# 01_Power.net
KiCad netlist of a schematic drawn in Altium Designer
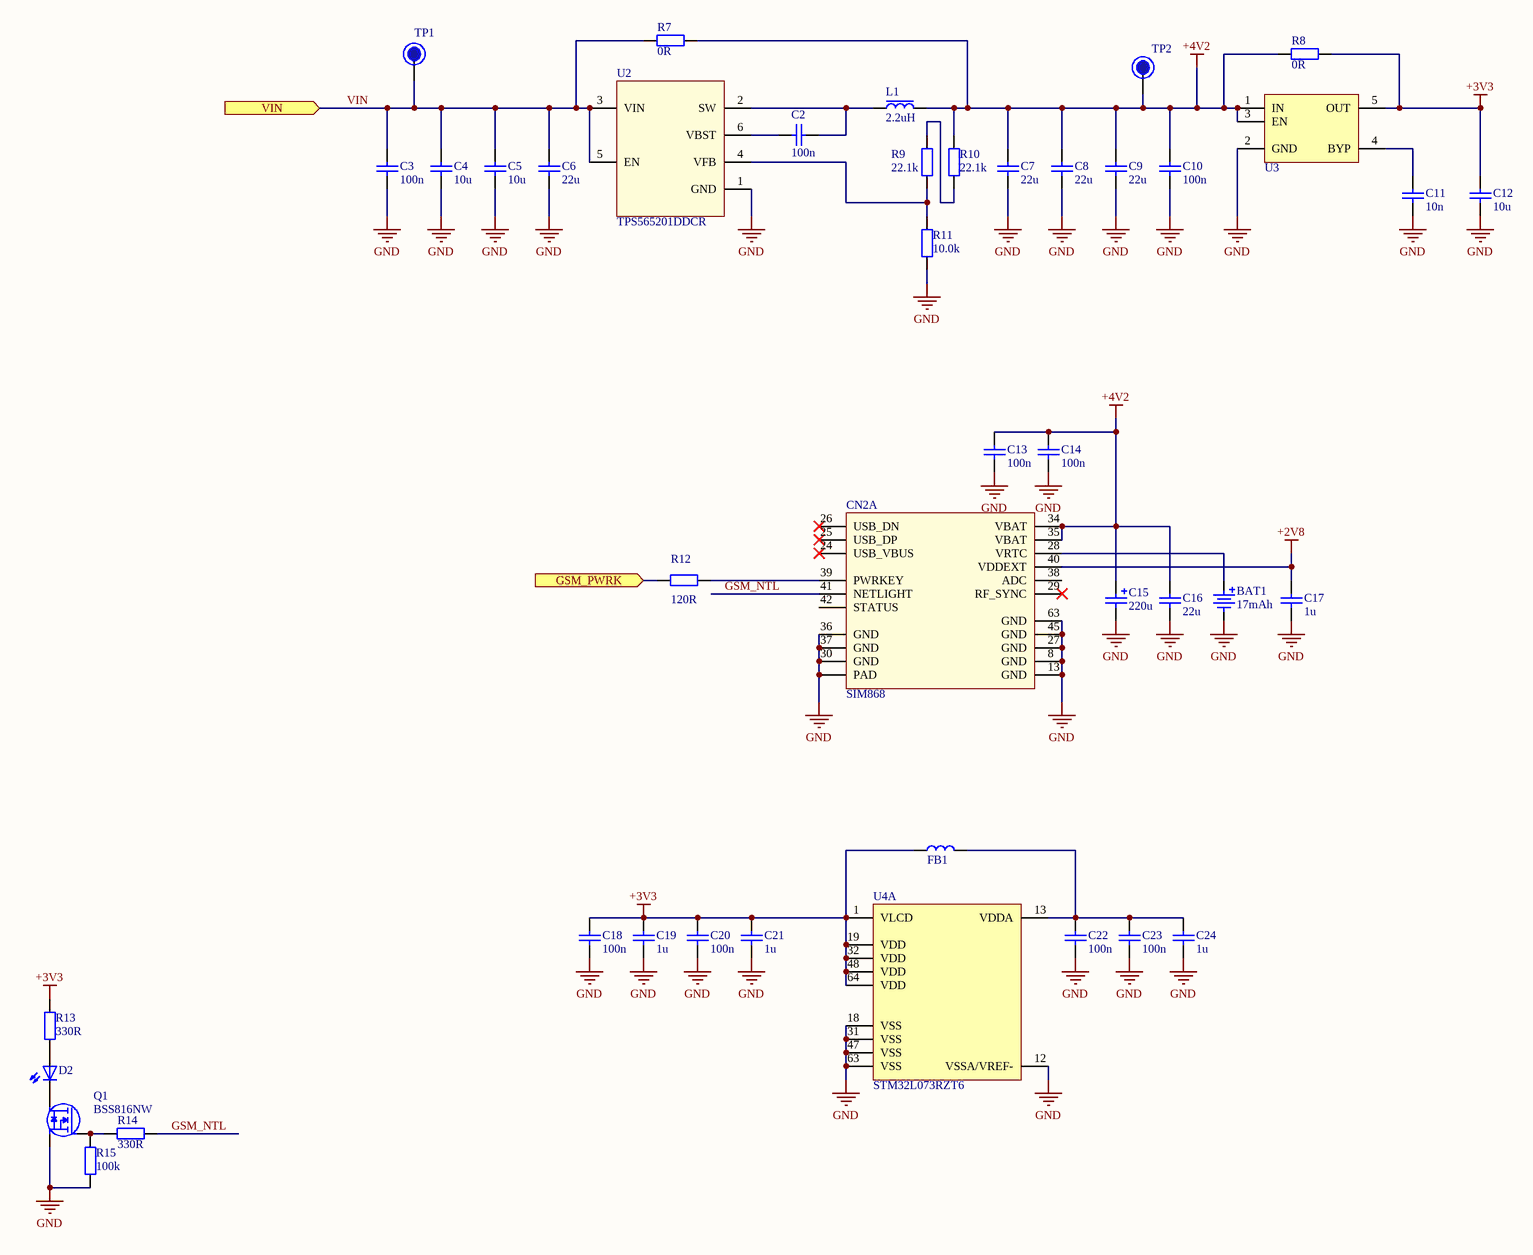
[diagram p0: 01_Power.SchDoc]

(export (version "E")
  (design (tool "Eeschema 10.0.6"))
  (components
    (comp (ref "BAT1")
      (value "17mAh")
      (footprint "ML1220")
      (description "BATT LITH 3V 17MAH COIN 12.5MM")
      (fields (field (name "MANUFACTURER") "CHINA") (field (name "MANUFACTURER PART NUMBER") "ML1220"))
      (libsource (lib "alfasat_lib") (part "ML1220"))
    )
    (comp (ref "C2")
      (value "100n")
      (footprint "C0603_IPC_MD")
      (description "CAP CER 0.1UF 16V X7R 0603")
      (fields
        (field (name "MANUFACTURER") "Samsung Electro-Mechanics")
        (field (name "MANUFACTURER PART NUMBER") "CL10B104KO8NNNC")
      )
      (libsource (lib "alfasat_parts_lib") (part "CL10B104KO8NNNC"))
    )
    (comp (ref "C3")
      (value "100n")
      (footprint "C0603_IPC_MD")
      (description "CAP CER 0.1UF 16V X7R 0603")
      (fields
        (field (name "MANUFACTURER") "Samsung Electro-Mechanics")
        (field (name "MANUFACTURER PART NUMBER") "CL10B104KO8NNNC")
      )
      (libsource (lib "alfasat_parts_lib") (part "CL10B104KO8NNNC"))
    )
    (comp (ref "C4")
      (value "10u")
      (footprint "C0805_IPC_MD")
      (description "CAP CER 10UF 16V X7R 0805")
      (fields
        (field (name "MANUFACTURER") "Samsung Electro-Mechanics")
        (field (name "MANUFACTURER PART NUMBER") "CL21B106KOQNNNG")
      )
      (libsource (lib "alfasat_parts_lib") (part "CL21B106KOQNNNG"))
    )
    (comp (ref "C5")
      (value "10u")
      (footprint "C0805_IPC_MD")
      (description "CAP CER 10UF 16V X7R 0805")
      (fields
        (field (name "MANUFACTURER") "Samsung Electro-Mechanics")
        (field (name "MANUFACTURER PART NUMBER") "CL21B106KOQNNNG")
      )
      (libsource (lib "alfasat_parts_lib") (part "CL21B106KOQNNNG"))
    )
    (comp (ref "C6")
      (value "22u")
      (footprint "C0805_IPC_MD")
      (description "CAP CER 22UF 16V X5R 0805")
      (fields
        (field (name "MANUFACTURER") "Samsung Electro-Mechanics")
        (field (name "MANUFACTURER PART NUMBER") "CL21A226MOCLRNC")
      )
      (libsource (lib "alfasat_parts_lib") (part "CL21A226MOCLRNC"))
    )
    (comp (ref "C7")
      (value "22u")
      (footprint "C0805_IPC_MD")
      (description "CAP CER 22UF 16V X5R 0805")
      (fields
        (field (name "MANUFACTURER") "Samsung Electro-Mechanics")
        (field (name "MANUFACTURER PART NUMBER") "CL21A226MOCLRNC")
      )
      (libsource (lib "alfasat_parts_lib") (part "CL21A226MOCLRNC"))
    )
    (comp (ref "C8")
      (value "22u")
      (footprint "C0805_IPC_MD")
      (description "CAP CER 22UF 16V X5R 0805")
      (fields
        (field (name "MANUFACTURER") "Samsung Electro-Mechanics")
        (field (name "MANUFACTURER PART NUMBER") "CL21A226MOCLRNC")
      )
      (libsource (lib "alfasat_parts_lib") (part "CL21A226MOCLRNC"))
    )
    (comp (ref "C9")
      (value "22u")
      (footprint "C0805_IPC_MD")
      (description "CAP CER 22UF 16V X5R 0805")
      (fields
        (field (name "MANUFACTURER") "Samsung Electro-Mechanics")
        (field (name "MANUFACTURER PART NUMBER") "CL21A226MOCLRNC")
      )
      (libsource (lib "alfasat_parts_lib") (part "CL21A226MOCLRNC"))
    )
    (comp (ref "C10")
      (value "100n")
      (footprint "C0603_IPC_MD")
      (description "CAP CER 0.1UF 16V X7R 0603")
      (fields
        (field (name "MANUFACTURER") "Samsung Electro-Mechanics")
        (field (name "MANUFACTURER PART NUMBER") "CL10B104KO8NNNC")
      )
      (libsource (lib "alfasat_parts_lib") (part "CL10B104KO8NNNC"))
    )
    (comp (ref "C11")
      (value "10n")
      (footprint "C0603_IPC_MD")
      (description "CAP CER 0.01UF 50V X7R 0603")
      (fields
        (field (name "MANUFACTURER") "Samsung Electro-Mechanics")
        (field (name "MANUFACTURER PART NUMBER") "CL10B103KB8NNNC")
      )
      (libsource (lib "alfasat_lib") (part "CL10B103KB8NNNC"))
    )
    (comp (ref "C12")
      (value "10u")
      (footprint "C0805_IPC_MD")
      (description "CAP CER 10UF 16V X7R 0805")
      (fields
        (field (name "MANUFACTURER") "Samsung Electro-Mechanics")
        (field (name "MANUFACTURER PART NUMBER") "CL21B106KOQNNNG")
      )
      (libsource (lib "alfasat_lib") (part "CL21B106KOQNNNG"))
    )
    (comp (ref "C13")
      (value "100n")
      (footprint "C0603_IPC_MD")
      (description "CAP CER 0.1UF 16V X7R 0603")
      (fields
        (field (name "MANUFACTURER") "Samsung Electro-Mechanics")
        (field (name "MANUFACTURER PART NUMBER") "CL10B104KO8WPNC")
      )
      (libsource (lib "alfasat_lib") (part "CL10B104KO8WPNC"))
    )
    (comp (ref "C14")
      (value "100n")
      (footprint "C0603_IPC_MD")
      (description "CAP CER 0.1UF 16V X7R 0603")
      (fields
        (field (name "MANUFACTURER") "Samsung Electro-Mechanics")
        (field (name "MANUFACTURER PART NUMBER") "CL10B104KO8WPNC")
      )
      (libsource (lib "alfasat_lib") (part "CL10B104KO8WPNC"))
    )
    (comp (ref "C15")
      (value "220u")
      (footprint "TANT_CAP_7343")
      (description "Tantalum Capacitors 220uF 6.3V CASE-D_7343 RoHS")
      (fields (field (name "MANUFACTURER") "PANASONIC") (field (name "MANUFACTURER PART NUMBER") "6TPE220MI"))
      (libsource (lib "alfasat_lib") (part "6TPE220MI"))
    )
    (comp (ref "C16")
      (value "22u")
      (footprint "C0805_IPC_MD")
      (description "CAP CER 22UF 16V X5R 0805")
      (fields
        (field (name "MANUFACTURER") "Samsung Electro-Mechanics")
        (field (name "MANUFACTURER PART NUMBER") "CL21A226MOCLRNC")
      )
      (libsource (lib "alfasat_lib") (part "CL21A226MOCLRNC"))
    )
    (comp (ref "C17")
      (value "1u")
      (footprint "C0603_IPC_MD")
      (description "CAP CER 1UF 16V X7R 0603")
      (fields
        (field (name "MANUFACTURER") "Samsung Electro-Mechanics")
        (field (name "MANUFACTURER PART NUMBER") "CL10B105MO8NNWC")
      )
      (libsource (lib "alfasat_lib") (part "CL10B105MO8NNWC"))
    )
    (comp (ref "C18")
      (value "100n")
      (footprint "C0603_IPC_MD")
      (description "CAP CER 0.1UF 16V X7R 0603")
      (fields
        (field (name "MANUFACTURER") "Samsung Electro-Mechanics")
        (field (name "MANUFACTURER PART NUMBER") "CL10B104KO8WPNC")
      )
      (libsource (lib "alfasat_lib") (part "CL10B104KO8WPNC"))
    )
    (comp (ref "C19")
      (value "1u")
      (footprint "C0603_IPC_MD")
      (description "CAP CER 1UF 16V X7R 0603")
      (fields
        (field (name "MANUFACTURER") "Samsung Electro-Mechanics")
        (field (name "MANUFACTURER PART NUMBER") "CL10B105MO8NNWC")
      )
      (libsource (lib "alfasat_lib") (part "CL10B105MO8NNWC"))
    )
    (comp (ref "C20")
      (value "100n")
      (footprint "C0603_IPC_MD")
      (description "CAP CER 0.1UF 16V X7R 0603")
      (fields
        (field (name "MANUFACTURER") "Samsung Electro-Mechanics")
        (field (name "MANUFACTURER PART NUMBER") "CL10B104KO8WPNC")
      )
      (libsource (lib "alfasat_lib") (part "CL10B104KO8WPNC"))
    )
    (comp (ref "C21")
      (value "1u")
      (footprint "C0603_IPC_MD")
      (description "CAP CER 1UF 16V X7R 0603")
      (fields
        (field (name "MANUFACTURER") "Samsung Electro-Mechanics")
        (field (name "MANUFACTURER PART NUMBER") "CL10B105MO8NNWC")
      )
      (libsource (lib "alfasat_lib") (part "CL10B105MO8NNWC"))
    )
    (comp (ref "C22")
      (value "100n")
      (footprint "C0603_IPC_MD")
      (description "CAP CER 0.1UF 16V X7R 0603")
      (fields
        (field (name "MANUFACTURER") "Samsung Electro-Mechanics")
        (field (name "MANUFACTURER PART NUMBER") "CL10B104KO8WPNC")
      )
      (libsource (lib "alfasat_lib") (part "CL10B104KO8WPNC"))
    )
    (comp (ref "C23")
      (value "100n")
      (footprint "C0603_IPC_MD")
      (description "CAP CER 0.1UF 16V X7R 0603")
      (fields
        (field (name "MANUFACTURER") "Samsung Electro-Mechanics")
        (field (name "MANUFACTURER PART NUMBER") "CL10B104KO8WPNC")
      )
      (libsource (lib "alfasat_lib") (part "CL10B104KO8WPNC"))
    )
    (comp (ref "C24")
      (value "1u")
      (footprint "C0603_IPC_MD")
      (description "CAP CER 1UF 16V X7R 0603")
      (fields
        (field (name "MANUFACTURER") "Samsung Electro-Mechanics")
        (field (name "MANUFACTURER PART NUMBER") "CL10B105MO8NNWC")
      )
      (libsource (lib "alfasat_lib") (part "CL10B105MO8NNWC"))
    )
    (comp (ref "CN2")
      (value "SIM868")
      (footprint "SIM868")
      (description "GSM & GPRS & GPS Modules PCBModule RoHS")
      (fields (field (name "MANUFACTURER") "SIMCom Wireless Solutions"))
      (libsource (lib "alfasat_lib") (part "SIM868"))
    )
    (comp (ref "D2")
      (value "LTST-C190GKT")
      (footprint "LED_0603")
      (description "LED GREEN CLEAR CHIP SMD 0603")
      (fields (field (name "MANUFACTURER") "Lite-On Inc."))
      (libsource (lib "alfasat_lib") (part "LTST-C190GKT"))
    )
    (comp (ref "FB1")
      (value "MH1608-601Y")
      (footprint "L0603_IPC_MD")
      (description "FERRITE BEAD 600R@100MHz 0603 for Power Line, 1000mA")
      (fields (field (name "MANUFACTURER") "Bourns Inc."))
      (libsource (lib "alfasat_lib") (part "MH1608-601Y"))
    )
    (comp (ref "L1")
      (value "2.2uH")
      (footprint "ASPI-0520LR")
      (description "FIXED IND 2.2UH 5.5A 36 MOHM SMD")
      (fields
        (field (name "MANUFACTURER") "Abracon LLC")
        (field (name "MANUFACTURER PART NUMBER") "ASPI-0520LR-2R2M-T2")
      )
      (libsource (lib "alfasat_parts_lib") (part "ASPI-0520LR-2R2M-T2"))
    )
    (comp (ref "Q1")
      (value "BSS816NW")
      (footprint "SOT323")
      (description "N-Channel Logic Level Enhancement Mode Field Effect Transistor")
      (fields (field (name "MANUFACTURER") "Infineon Technologies"))
      (libsource (lib "alfasat_lib") (part "BSS816"))
    )
    (comp (ref "R7")
      (value "0R")
      (footprint "R0603_IPC_MD")
      (description "RES SMD 0 OHM JUMPER 1/10W 0603")
      (fields
        (field (name "MANUFACTURER") "Bourns Inc.")
        (field (name "MANUFACTURER PART NUMBER") "CR0603-J/-000ELF")
      )
      (libsource (lib "alfasat_parts_lib") (part "CR0603-J/-000ELF"))
    )
    (comp (ref "R8")
      (value "0R")
      (footprint "R0603_IPC_MD")
      (description "RES SMD 0 OHM JUMPER 1/10W 0603")
      (fields
        (field (name "MANUFACTURER") "Bourns Inc.")
        (field (name "MANUFACTURER PART NUMBER") "CR0603-J/-000ELF")
      )
      (libsource (lib "alfasat_parts_lib") (part "CR0603-J/-000ELF"))
    )
    (comp (ref "R9")
      (value "22.1k")
      (footprint "R0603_IPC_MD")
      (description "RES SMD 22.1K OHM 1% 1/10W 0603")
      (fields
        (field (name "MANUFACTURER") "Yageo")
        (field (name "MANUFACTURER PART NUMBER") "RC0603FR-0722K1L")
      )
      (libsource (lib "alfasat_parts_lib") (part "RC0603FR-0722K1L"))
    )
    (comp (ref "R10")
      (value "22.1k")
      (footprint "R0603_IPC_MD")
      (description "RES SMD 22.1K OHM 1% 1/10W 0603")
      (fields
        (field (name "MANUFACTURER") "Yageo")
        (field (name "MANUFACTURER PART NUMBER") "RC0603FR-0722K1L")
      )
      (libsource (lib "alfasat_parts_lib") (part "RC0603FR-0722K1L"))
    )
    (comp (ref "R11")
      (value "10.0k")
      (footprint "R0603_IPC_MD")
      (description "RES 10K OHM 1% 1/10W 0603")
      (fields
        (field (name "MANUFACTURER") "Stackpole Electronics Inc")
        (field (name "MANUFACTURER PART NUMBER") "RMCF0603FT10K0")
      )
      (libsource (lib "alfasat_parts_lib") (part "RMCF0603FT10K0"))
    )
    (comp (ref "R12")
      (value "120R")
      (footprint "R0603_IPC_MD")
      (description "RES SMD 120 OHM 5% 1/10W 0603")
      (fields
        (field (name "MANUFACTURER") "Yageo")
        (field (name "MANUFACTURER PART NUMBER") "RC0603JR-07120RL")
      )
      (libsource (lib "alfasat_lib") (part "RC0603JR-07120RL"))
    )
    (comp (ref "R13")
      (value "330R")
      (footprint "R0603_IPC_MD")
      (description "RES SMD 330 OHM 5% 1/10W 0603")
      (fields
        (field (name "MANUFACTURER") "Bourns Inc.")
        (field (name "MANUFACTURER PART NUMBER") "CR0603-JW-331ELF")
      )
      (libsource (lib "alfasat_lib") (part "CR0603-JW-331ELF"))
    )
    (comp (ref "R14")
      (value "330R")
      (footprint "R0603_IPC_MD")
      (description "RES SMD 330 OHM 5% 1/10W 0603")
      (fields
        (field (name "MANUFACTURER") "Bourns Inc.")
        (field (name "MANUFACTURER PART NUMBER") "CR0603-JW-331ELF")
      )
      (libsource (lib "") (part "CR0603-JW-331ELF_1"))
    )
    (comp (ref "R15")
      (value "100k")
      (footprint "R0603_IPC_MD")
      (description "RES 100K OHM 1% 1/10W 0603")
      (fields
        (field (name "MANUFACTURER") "Bourns Inc.")
        (field (name "MANUFACTURER PART NUMBER") "RMCF0603FT100K")
      )
      (libsource (lib "alfasat_lib") (part "RMCF0603FT100K"))
    )
    (comp (ref "TP1")
      (value "VIN")
      (footprint "TestPoint_1M5")
      (description "Test Point")
      (libsource (lib "alfasat_parts_lib") (part "TP"))
    )
    (comp (ref "TP2")
      (value "4V2")
      (footprint "TestPoint_1M5")
      (description "Test Point")
      (libsource (lib "alfasat_parts_lib") (part "TP"))
    )
    (comp (ref "U2")
      (value "TPS565201DDCR")
      (footprint "SOT23-6_(TI)")
      (description "Buck Switching Regulator IC Positive Adjustable 0.76V 1 Output 5A SOT-23-6 Thin, TSOT-23-6")
      (fields (field (name "MANUFACTURER") "TI"))
      (libsource (lib "alfasat_parts_lib") (part "TPS565201DDCR"))
    )
    (comp (ref "U3")
      (value "MIC5219-3.3YM5-TR")
      (footprint "SOT23-5_(MT)")
      (description "IC REG LINEAR 3.3V 500MA SOT23-5")
      (fields (field (name "MANUFACTURER") "Microchip Technology"))
      (libsource (lib "alfasat_lib") (part "MIC5219-3.3YM5-TR"))
    )
    (comp (ref "U4")
      (value "STM32L073RZT6")
      (footprint "LQFP64_10X10MM")
      (description "Ultra-low-power 32-bit MCU ARM®-based Cortex®-M0+")
      (fields (field (name "MANUFACTURER") "ST"))
      (libsource (lib "alfasat_lib") (part "STM32L073RZT6"))
    )
  )
  (nets
    (net (code "1") (name "+2V8") (class "Default")
      (node (ref "C17") (pin "2") (pinfunction "2_2") (pintype "passive"))
      (node (ref "CN2") (pin "40") (pinfunction "VDDEXT_40") (pintype "passive"))
    )
    (net (code "2") (name "+3V3") (class "Default")
      (node (ref "C12") (pin "2") (pinfunction "2_2") (pintype "passive"))
      (node (ref "C18") (pin "2") (pinfunction "2_2") (pintype "passive"))
      (node (ref "C19") (pin "2") (pinfunction "2_2") (pintype "passive"))
      (node (ref "C20") (pin "2") (pinfunction "2_2") (pintype "passive"))
      (node (ref "C21") (pin "2") (pinfunction "2_2") (pintype "passive"))
      (node (ref "FB1") (pin "1") (pinfunction "1_1") (pintype "passive"))
      (node (ref "R13") (pin "2") (pinfunction "2_2") (pintype "passive"))
      (node (ref "R8") (pin "2") (pinfunction "2_2") (pintype "passive"))
      (node (ref "U3") (pin "5") (pinfunction "OUT_5") (pintype "passive"))
      (node (ref "U4") (pin "1") (pinfunction "VLCD_1") (pintype "power_in"))
      (node (ref "U4") (pin "19") (pinfunction "VDD_19") (pintype "power_in"))
      (node (ref "U4") (pin "32") (pinfunction "VDD_32") (pintype "power_in"))
      (node (ref "U4") (pin "48") (pinfunction "VDD_48") (pintype "power_in"))
      (node (ref "U4") (pin "64") (pinfunction "VDD_64") (pintype "power_in"))
    )
    (net (code "3") (name "+4V2") (class "Default")
      (node (ref "C10") (pin "1") (pinfunction "1_1") (pintype "passive"))
      (node (ref "C13") (pin "2") (pinfunction "2_2") (pintype "passive"))
      (node (ref "C14") (pin "2") (pinfunction "2_2") (pintype "passive"))
      (node (ref "C15") (pin "1") (pinfunction "1_1") (pintype "passive"))
      (node (ref "C16") (pin "1") (pinfunction "1_1") (pintype "passive"))
      (node (ref "C7") (pin "1") (pinfunction "1_1") (pintype "passive"))
      (node (ref "C8") (pin "1") (pinfunction "1_1") (pintype "passive"))
      (node (ref "C9") (pin "1") (pinfunction "1_1") (pintype "passive"))
      (node (ref "CN2") (pin "34") (pinfunction "VBAT_34") (pintype "power_in"))
      (node (ref "CN2") (pin "35") (pinfunction "VBAT_35") (pintype "power_in"))
      (node (ref "L1") (pin "2") (pinfunction "2_2") (pintype "passive"))
      (node (ref "R10") (pin "2") (pinfunction "2_2") (pintype "passive"))
      (node (ref "R7") (pin "2") (pinfunction "2_2") (pintype "passive"))
      (node (ref "R8") (pin "1") (pinfunction "1_1") (pintype "passive"))
      (node (ref "TP2") (pin "0") (pinfunction "0_0") (pintype "passive"))
      (node (ref "U3") (pin "1") (pinfunction "IN_1") (pintype "passive"))
      (node (ref "U3") (pin "3") (pinfunction "EN_3") (pintype "passive"))
    )
    (net (code "4") (name "/GSM_NTL") (class "Default")
      (node (ref "CN2") (pin "41") (pinfunction "NETLIGHT_41") (pintype "passive"))
      (node (ref "R14") (pin "2") (pinfunction "2_2") (pintype "passive"))
    )
    (net (code "5") (name "/GSM_PWRK") (class "Default")
      (node (ref "R12") (pin "1") (pinfunction "1_1") (pintype "passive"))
    )
    (net (code "6") (name "/VIN") (class "Default")
      (node (ref "C3") (pin "1") (pinfunction "1_1") (pintype "passive"))
      (node (ref "C4") (pin "2") (pinfunction "2_2") (pintype "passive"))
      (node (ref "C5") (pin "2") (pinfunction "2_2") (pintype "passive"))
      (node (ref "C6") (pin "1") (pinfunction "1_1") (pintype "passive"))
      (node (ref "R7") (pin "1") (pinfunction "1_1") (pintype "passive"))
      (node (ref "TP1") (pin "0") (pinfunction "0_0") (pintype "passive"))
      (node (ref "U2") (pin "3") (pinfunction "VIN_3") (pintype "passive"))
      (node (ref "U2") (pin "5") (pinfunction "EN_5") (pintype "passive"))
    )
    (net (code "7") (name "GND") (class "Default")
      (node (ref "BAT1") (pin "2") (pinfunction "2_2") (pintype "passive"))
      (node (ref "C10") (pin "2") (pinfunction "2_2") (pintype "passive"))
      (node (ref "C11") (pin "1") (pinfunction "1_1") (pintype "passive"))
      (node (ref "C12") (pin "1") (pinfunction "1_1") (pintype "passive"))
      (node (ref "C13") (pin "1") (pinfunction "1_1") (pintype "passive"))
      (node (ref "C14") (pin "1") (pinfunction "1_1") (pintype "passive"))
      (node (ref "C15") (pin "2") (pinfunction "2_2") (pintype "passive"))
      (node (ref "C16") (pin "2") (pinfunction "2_2") (pintype "passive"))
      (node (ref "C17") (pin "1") (pinfunction "1_1") (pintype "passive"))
      (node (ref "C18") (pin "1") (pinfunction "1_1") (pintype "passive"))
      (node (ref "C19") (pin "1") (pinfunction "1_1") (pintype "passive"))
      (node (ref "C20") (pin "1") (pinfunction "1_1") (pintype "passive"))
      (node (ref "C21") (pin "1") (pinfunction "1_1") (pintype "passive"))
      (node (ref "C22") (pin "1") (pinfunction "1_1") (pintype "passive"))
      (node (ref "C23") (pin "1") (pinfunction "1_1") (pintype "passive"))
      (node (ref "C24") (pin "1") (pinfunction "1_1") (pintype "passive"))
      (node (ref "C3") (pin "2") (pinfunction "2_2") (pintype "passive"))
      (node (ref "C4") (pin "1") (pinfunction "1_1") (pintype "passive"))
      (node (ref "C5") (pin "1") (pinfunction "1_1") (pintype "passive"))
      (node (ref "C6") (pin "2") (pinfunction "2_2") (pintype "passive"))
      (node (ref "C7") (pin "2") (pinfunction "2_2") (pintype "passive"))
      (node (ref "C8") (pin "2") (pinfunction "2_2") (pintype "passive"))
      (node (ref "C9") (pin "2") (pinfunction "2_2") (pintype "passive"))
      (node (ref "CN2") (pin "13") (pinfunction "GND_13") (pintype "passive"))
      (node (ref "CN2") (pin "27") (pinfunction "GND_27") (pintype "passive"))
      (node (ref "CN2") (pin "30") (pinfunction "GND_30") (pintype "passive"))
      (node (ref "CN2") (pin "36") (pinfunction "GND_36") (pintype "passive"))
      (node (ref "CN2") (pin "37") (pinfunction "GND_37") (pintype "passive"))
      (node (ref "CN2") (pin "45") (pinfunction "GND_45") (pintype "passive"))
      (node (ref "CN2") (pin "63") (pinfunction "GND_63") (pintype "passive"))
      (node (ref "CN2") (pin "8") (pinfunction "GND_8") (pintype "passive"))
      (node (ref "CN2") (pin "PAD") (pinfunction "PAD_PAD") (pintype "passive"))
      (node (ref "Q1") (pin "2") (pinfunction "S_2") (pintype "passive"))
      (node (ref "R11") (pin "1") (pinfunction "1_1") (pintype "passive"))
      (node (ref "R15") (pin "1") (pinfunction "1_1") (pintype "passive"))
      (node (ref "U2") (pin "1") (pinfunction "GND_1") (pintype "passive"))
      (node (ref "U3") (pin "2") (pinfunction "GND_2") (pintype "passive"))
      (node (ref "U4") (pin "12") (pinfunction "VSSA/VREF-_12") (pintype "power_in"))
      (node (ref "U4") (pin "18") (pinfunction "VSS_18") (pintype "power_in"))
      (node (ref "U4") (pin "31") (pinfunction "VSS_31") (pintype "power_in"))
      (node (ref "U4") (pin "47") (pinfunction "VSS_47") (pintype "power_in"))
      (node (ref "U4") (pin "63") (pinfunction "VSS_63") (pintype "power_in"))
    )
    (net (code "8") (name "Net-(CN2A-PWRKEY)") (class "Default")
      (node (ref "CN2") (pin "39") (pinfunction "PWRKEY_39") (pintype "passive"))
      (node (ref "R12") (pin "2") (pinfunction "2_2") (pintype "passive"))
    )
    (net (code "9") (name "Net-(CN2A-VRTC)") (class "Default")
      (node (ref "BAT1") (pin "1") (pinfunction "1_1") (pintype "passive"))
      (node (ref "CN2") (pin "28") (pinfunction "VRTC_28") (pintype "passive"))
    )
    (net (code "10") (name "Net-(D2-A)") (class "Default")
      (node (ref "D2") (pin "2") (pinfunction "A_2") (pintype "passive"))
      (node (ref "R13") (pin "1") (pinfunction "1_1") (pintype "passive"))
    )
    (net (code "11") (name "Net-(D2-C)") (class "Default")
      (node (ref "D2") (pin "1") (pinfunction "C_1") (pintype "passive"))
      (node (ref "Q1") (pin "3") (pinfunction "D_3") (pintype "passive"))
    )
    (net (code "12") (name "Net-(Q1-G)") (class "Default")
      (node (ref "Q1") (pin "1") (pinfunction "G_1") (pintype "passive"))
      (node (ref "R14") (pin "1") (pinfunction "1_1") (pintype "passive"))
      (node (ref "R15") (pin "2") (pinfunction "2_2") (pintype "passive"))
    )
    (net (code "13") (name "Net-(R10-Pad1)") (class "Default")
      (node (ref "R10") (pin "1") (pinfunction "1_1") (pintype "passive"))
      (node (ref "R9") (pin "2") (pinfunction "2_2") (pintype "passive"))
    )
    (net (code "14") (name "Net-(U2-SW)") (class "Default")
      (node (ref "C2") (pin "1") (pinfunction "1_1") (pintype "passive"))
      (node (ref "L1") (pin "1") (pinfunction "1_1") (pintype "passive"))
      (node (ref "U2") (pin "2") (pinfunction "SW_2") (pintype "passive"))
    )
    (net (code "15") (name "Net-(U2-VBST)") (class "Default")
      (node (ref "C2") (pin "2") (pinfunction "2_2") (pintype "passive"))
      (node (ref "U2") (pin "6") (pinfunction "VBST_6") (pintype "passive"))
    )
    (net (code "16") (name "Net-(U2-VFB)") (class "Default")
      (node (ref "R11") (pin "2") (pinfunction "2_2") (pintype "passive"))
      (node (ref "R9") (pin "1") (pinfunction "1_1") (pintype "passive"))
      (node (ref "U2") (pin "4") (pinfunction "VFB_4") (pintype "passive"))
    )
    (net (code "17") (name "Net-(U3-BYP)") (class "Default")
      (node (ref "C11") (pin "2") (pinfunction "2_2") (pintype "passive"))
      (node (ref "U3") (pin "4") (pinfunction "BYP_4") (pintype "passive"))
    )
    (net (code "18") (name "Net-(U4A-VDDA)") (class "Default")
      (node (ref "C22") (pin "2") (pinfunction "2_2") (pintype "passive"))
      (node (ref "C23") (pin "2") (pinfunction "2_2") (pintype "passive"))
      (node (ref "C24") (pin "2") (pinfunction "2_2") (pintype "passive"))
      (node (ref "FB1") (pin "2") (pinfunction "2_2") (pintype "passive"))
      (node (ref "U4") (pin "13") (pinfunction "VDDA_13") (pintype "power_in"))
    )
    (net (code "19") (name "unconnected-(CN2A-ADC-Pad38)") (class "Default")
      (node (ref "CN2") (pin "38") (pinfunction "ADC_38") (pintype "passive"))
    )
    (net (code "20") (name "unconnected-(CN2A-RF_SYNC-Pad29)") (class "Default")
      (node (ref "CN2") (pin "29") (pinfunction "RF_SYNC_29") (pintype "passive+no_connect"))
    )
    (net (code "21") (name "unconnected-(CN2A-STATUS-Pad42)") (class "Default")
      (node (ref "CN2") (pin "42") (pinfunction "STATUS_42") (pintype "passive"))
    )
    (net (code "22") (name "unconnected-(CN2A-USB_DN-Pad26)") (class "Default")
      (node (ref "CN2") (pin "26") (pinfunction "USB_DN_26") (pintype "passive+no_connect"))
    )
    (net (code "23") (name "unconnected-(CN2A-USB_DP-Pad25)") (class "Default")
      (node (ref "CN2") (pin "25") (pinfunction "USB_DP_25") (pintype "passive+no_connect"))
    )
    (net (code "24") (name "unconnected-(CN2A-USB_VBUS-Pad24)") (class "Default")
      (node (ref "CN2") (pin "24") (pinfunction "USB_VBUS_24") (pintype "passive+no_connect"))
    )
  )
)
